# SolderingStation_Control.net
KiCad netlist of a schematic drawn in Altium Designer
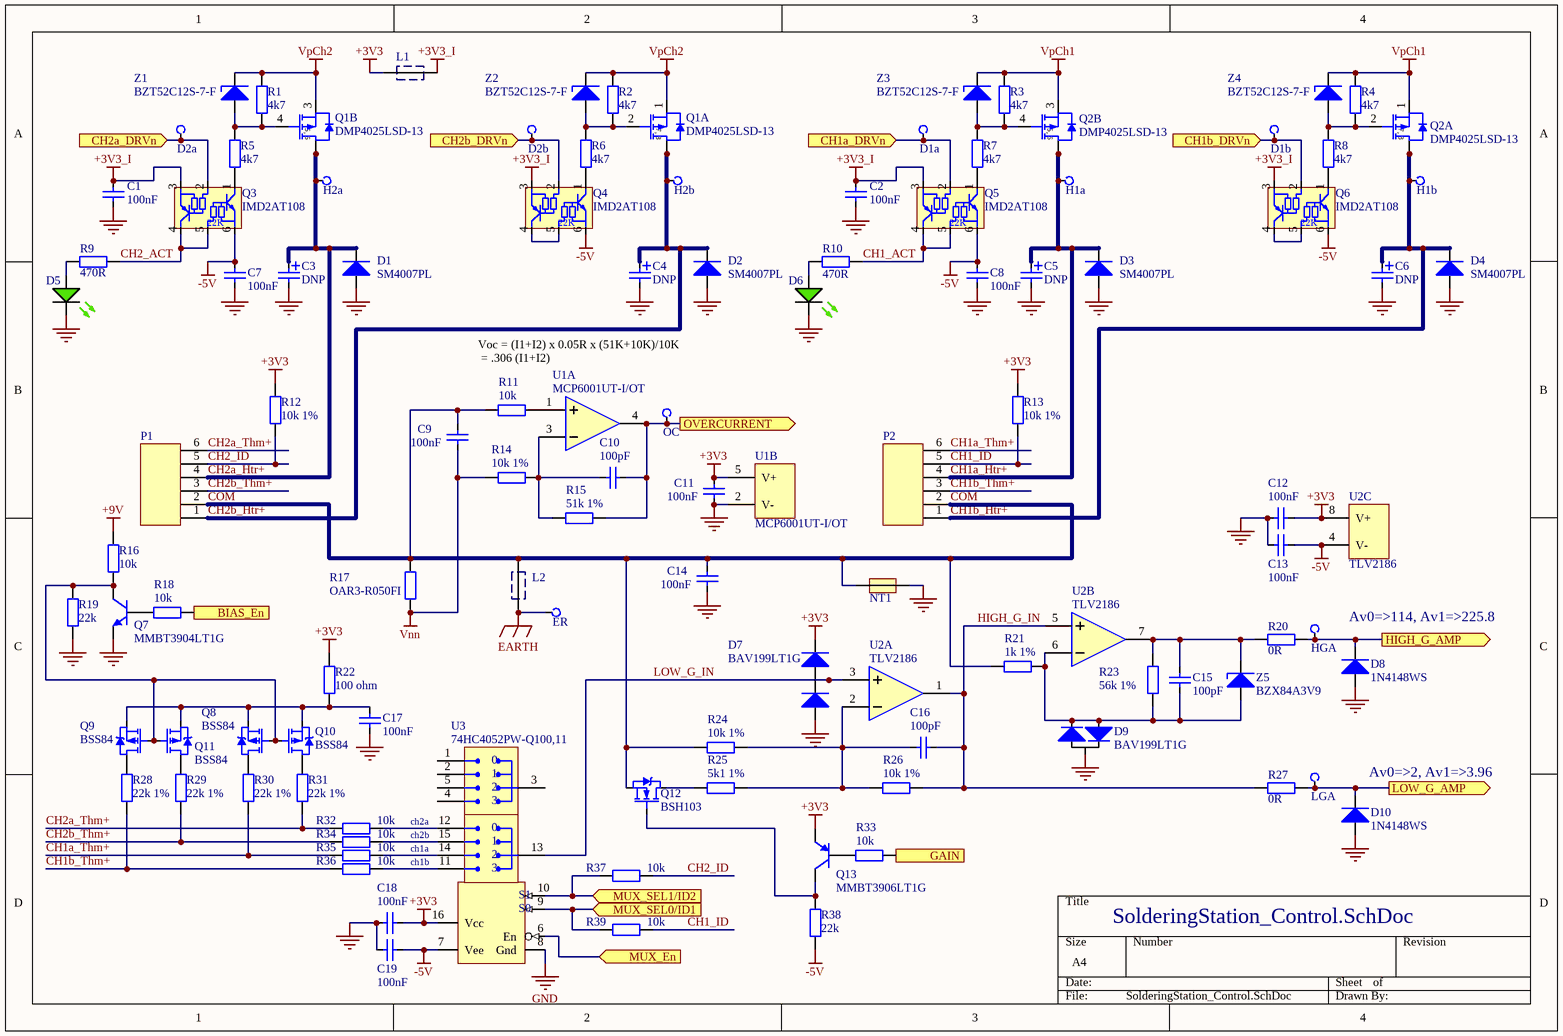
[diagram p0: SolderingStation_Control.SchDoc]

(export (version "E")
  (design (tool "Eeschema 10.0.6"))
  (components
    (comp (ref "C1")
      (value "100nF")
      (footprint "CCNP1608-0603")
      (description "Capacitor non-polar SMT 0603")
      (fields
        (field (name "MANUFACTURER") "Generic Components")
        (field (name "PUBLISHER") "Altium Hobart Technology Centre")
      )
      (libsource (lib "MyLibrary") (part "Cap_CCNP_0603"))
    )
    (comp (ref "C2")
      (value "100nF")
      (footprint "CCNP1608-0603")
      (description "Capacitor non-polar SMT 0603")
      (fields
        (field (name "MANUFACTURER") "Generic Components")
        (field (name "PUBLISHER") "Altium Hobart Technology Centre")
      )
      (libsource (lib "MyLibrary") (part "Cap_CCNP_0603"))
    )
    (comp (ref "C3")
      (value "DNP")
      (footprint "CC2012-0805")
      (description "Capacitor SMT 0805")
      (fields
        (field (name "MANUFACTURER") "Generic Components")
        (field (name "PUBLISHER") "Altium Hobart Technology Centre")
      )
      (libsource (lib "MyLibrary") (part "Cap_CC_0805"))
    )
    (comp (ref "C4")
      (value "DNP")
      (footprint "CC2012-0805")
      (description "Capacitor SMT 0805")
      (fields
        (field (name "MANUFACTURER") "Generic Components")
        (field (name "PUBLISHER") "Altium Hobart Technology Centre")
      )
      (libsource (lib "MyLibrary") (part "Cap_CC_0805"))
    )
    (comp (ref "C5")
      (value "DNP")
      (footprint "CC2012-0805")
      (description "Capacitor SMT 0805")
      (fields
        (field (name "MANUFACTURER") "Generic Components")
        (field (name "PUBLISHER") "Altium Hobart Technology Centre")
      )
      (libsource (lib "MyLibrary") (part "Cap_CC_0805"))
    )
    (comp (ref "C6")
      (value "DNP")
      (footprint "CC2012-0805")
      (description "Capacitor SMT 0805")
      (fields
        (field (name "MANUFACTURER") "Generic Components")
        (field (name "PUBLISHER") "Altium Hobart Technology Centre")
      )
      (libsource (lib "MyLibrary") (part "Cap_CC_0805"))
    )
    (comp (ref "C7")
      (value "100nF")
      (footprint "CCNP1608-0603")
      (description "Capacitor non-polar SMT 0603")
      (fields
        (field (name "MANUFACTURER") "Generic Components")
        (field (name "PUBLISHER") "Altium Hobart Technology Centre")
      )
      (libsource (lib "MyLibrary") (part "Cap_CCNP_0603"))
    )
    (comp (ref "C8")
      (value "100nF")
      (footprint "CCNP1608-0603")
      (description "Capacitor non-polar SMT 0603")
      (fields
        (field (name "MANUFACTURER") "Generic Components")
        (field (name "PUBLISHER") "Altium Hobart Technology Centre")
      )
      (libsource (lib "MyLibrary") (part "Cap_CCNP_0603"))
    )
    (comp (ref "C9")
      (value "100nF")
      (footprint "CCNP1608-0603")
      (description "Capacitor non-polar SMT 0603")
      (fields
        (field (name "MANUFACTURER") "Generic Components")
        (field (name "PUBLISHER") "Altium Hobart Technology Centre")
      )
      (libsource (lib "MyLibrary") (part "Cap_CCNP_0603"))
    )
    (comp (ref "C10")
      (value "100pF")
      (footprint "CCNP1608-0603")
      (description "Capacitor non-polar SMT 0603")
      (fields
        (field (name "MANUFACTURER") "Generic Components")
        (field (name "PUBLISHER") "Altium Hobart Technology Centre")
      )
      (libsource (lib "MyLibrary") (part "Cap_CCNP_0603"))
    )
    (comp (ref "C11")
      (value "100nF")
      (footprint "CCNP1608-0603")
      (description "Capacitor non-polar SMT 0603")
      (fields
        (field (name "MANUFACTURER") "Generic Components")
        (field (name "PUBLISHER") "Altium Hobart Technology Centre")
      )
      (libsource (lib "MyLibrary") (part "Cap_CCNP_0603"))
    )
    (comp (ref "C12")
      (value "100nF")
      (footprint "CCNP1608-0603")
      (description "Capacitor non-polar SMT 0603")
      (fields
        (field (name "MANUFACTURER") "Generic Components")
        (field (name "PUBLISHER") "Altium Hobart Technology Centre")
      )
      (libsource (lib "MyLibrary") (part "Cap_CCNP_0603"))
    )
    (comp (ref "C13")
      (value "100nF")
      (footprint "CCNP1608-0603")
      (description "Capacitor non-polar SMT 0603")
      (fields
        (field (name "MANUFACTURER") "Generic Components")
        (field (name "PUBLISHER") "Altium Hobart Technology Centre")
      )
      (libsource (lib "MyLibrary") (part "Cap_CCNP_0603"))
    )
    (comp (ref "C14")
      (value "100nF")
      (footprint "CCNP1608-0603")
      (description "Capacitor non-polar SMT 0603")
      (fields
        (field (name "MANUFACTURER") "Generic Components")
        (field (name "PUBLISHER") "Altium Hobart Technology Centre")
      )
      (libsource (lib "MyLibrary") (part "Cap_CCNP_0603"))
    )
    (comp (ref "C15")
      (value "100pF")
      (footprint "CCNP1608-0603")
      (description "Capacitor non-polar SMT 0603")
      (fields
        (field (name "MANUFACTURER") "Generic Components")
        (field (name "PUBLISHER") "Altium Hobart Technology Centre")
      )
      (libsource (lib "MyLibrary") (part "Cap_CCNP_0603"))
    )
    (comp (ref "C16")
      (value "100pF")
      (footprint "CCNP1608-0603")
      (description "Capacitor non-polar SMT 0603")
      (fields
        (field (name "MANUFACTURER") "Generic Components")
        (field (name "PUBLISHER") "Altium Hobart Technology Centre")
      )
      (libsource (lib "MyLibrary") (part "Cap_CCNP_0603"))
    )
    (comp (ref "C17")
      (value "100nF")
      (footprint "CCNP1608-0603")
      (description "Capacitor non-polar SMT 0603")
      (fields
        (field (name "MANUFACTURER") "Generic Components")
        (field (name "PUBLISHER") "Altium Hobart Technology Centre")
      )
      (libsource (lib "MyLibrary") (part "Cap_CCNP_0603"))
    )
    (comp (ref "C18")
      (value "100nF")
      (footprint "CCNP1608-0603")
      (description "Capacitor non-polar SMT 0603")
      (fields
        (field (name "MANUFACTURER") "Generic Components")
        (field (name "PUBLISHER") "Altium Hobart Technology Centre")
      )
      (libsource (lib "MyLibrary") (part "Cap_CCNP_0603"))
    )
    (comp (ref "C19")
      (value "100nF")
      (footprint "CCNP1608-0603")
      (description "Capacitor non-polar SMT 0603")
      (fields
        (field (name "MANUFACTURER") "Generic Components")
        (field (name "PUBLISHER") "Altium Hobart Technology Centre")
      )
      (libsource (lib "MyLibrary") (part "Cap_CCNP_0603"))
    )
    (comp (ref "D1")
      (value "SM4007PL")
      (footprint "SOD-123FL")
      (description "Diodes - General Purpose, 1kV 1A 1.1V 1A SOD-123FL")
      (libsource (lib "MyLibrary") (part "SM4007PL"))
    )
    (comp (ref "D1a")
      (value "Drive1")
      (footprint "PCBPIN - 0.7mm")
      (description "Test Point")
      (libsource (lib "MySchLib") (part "TP"))
    )
    (comp (ref "D1b")
      (value "Drive2")
      (footprint "PCBPIN - 0.7mm")
      (description "Test Point")
      (libsource (lib "MySchLib") (part "TP"))
    )
    (comp (ref "D2")
      (value "SM4007PL")
      (footprint "SOD-123FL")
      (description "Diodes - General Purpose, 1kV 1A 1.1V 1A SOD-123FL")
      (libsource (lib "MyLibrary") (part "SM4007PL"))
    )
    (comp (ref "D2a")
      (value "Drive2")
      (footprint "PCBPIN - 0.7mm")
      (description "Test Point")
      (libsource (lib "MySchLib") (part "TP"))
    )
    (comp (ref "D2b")
      (value "Drive2")
      (footprint "PCBPIN - 0.7mm")
      (description "Test Point")
      (libsource (lib "MySchLib") (part "TP"))
    )
    (comp (ref "D3")
      (value "SM4007PL")
      (footprint "SOD-123FL")
      (description "Diodes - General Purpose, 1kV 1A 1.1V 1A SOD-123FL")
      (libsource (lib "MyLibrary") (part "SM4007PL"))
    )
    (comp (ref "D4")
      (value "SM4007PL")
      (footprint "SOD-123FL")
      (description "Diodes - General Purpose, 1kV 1A 1.1V 1A SOD-123FL")
      (libsource (lib "MyLibrary") (part "SM4007PL"))
    )
    (comp (ref "D5")
      (value "LED")
      (footprint "LED3MM-GREEN - 10mm Proud")
      (description "3mm Green LED")
      (fields (field (name "MANUFACTURER") "Generic Components") (field (name "PUBLISHER") "Altium Limited"))
      (libsource (lib "MySchLib") (part "LED_3MM_GREEN"))
    )
    (comp (ref "D6")
      (value "LED")
      (footprint "LED3MM-GREEN - 10mm Proud")
      (description "3mm Green LED")
      (fields (field (name "MANUFACTURER") "Generic Components") (field (name "PUBLISHER") "Altium Limited"))
      (libsource (lib "MySchLib") (part "LED_3MM_GREEN"))
    )
    (comp (ref "D7")
      (value "BAV199LT1G")
      (footprint "SOT23_M")
      (description "Dual Series low-leakage switching diodes, 3-Pin SOT-23")
      (libsource (lib "MySchLib") (part "BAV199LT1G"))
    )
    (comp (ref "D8")
      (value "1N4148WS")
      (footprint "SOD-323")
      (description "Switching Diode 100V 150mA 1.25V@150mA 4ns SOD-323")
      (libsource (lib "MyLibrary") (part "1N4148WS"))
    )
    (comp (ref "D9")
      (value "BAV199LT1G")
      (footprint "SOT23_M")
      (description "Dual Series low-leakage switching diodes, 3-Pin SOT-23")
      (libsource (lib "MyLibrary") (part "BAV199LT1G"))
    )
    (comp (ref "D10")
      (value "1N4148WS")
      (footprint "SOD-323")
      (description "Switching Diode 100V 150mA 1.25V@150mA 4ns SOD-323")
      (libsource (lib "MyLibrary") (part "1N4148WS"))
    )
    (comp (ref "ER")
      (value "Gnd")
      (footprint "PCBPIN - 0.7mm")
      (description "Test Point")
      (libsource (lib "") (part "TP_1"))
    )
    (comp (ref "H1a")
      (value "Heater1")
      (footprint "PCBPIN - 0.7mm")
      (description "Test Point")
      (libsource (lib "") (part "TP_1"))
    )
    (comp (ref "H1b")
      (value "Heater2")
      (footprint "PCBPIN - 0.7mm")
      (description "Test Point")
      (libsource (lib "") (part "TP_1"))
    )
    (comp (ref "H2a")
      (value "Heater2")
      (footprint "PCBPIN - 0.7mm")
      (description "Test Point")
      (libsource (lib "") (part "TP_1"))
    )
    (comp (ref "H2b")
      (value "Heater2")
      (footprint "PCBPIN - 0.7mm")
      (description "Test Point")
      (libsource (lib "") (part "TP_1"))
    )
    (comp (ref "HGA")
      (value "TC1")
      (footprint "PCBPIN - 0.7mm")
      (description "Test Point")
      (libsource (lib "MySchLib") (part "TP"))
    )
    (comp (ref "L1")
      (value "Ferrite Bead")
      (footprint "FB2012-0805")
      (description "Ferrite Bead SMT 0805, TDK MPZ2012S102AT, 0.15OHM, 1.5A")
      (libsource (lib "MySchLib") (part "Ferrite Bead 0805"))
    )
    (comp (ref "L2")
      (value "Ferrite Bead")
      (footprint "FB2012-0805")
      (description "Ferrite Bead SMT 0805, TDK MPZ2012S102AT, 0.15OHM, 1.5A")
      (libsource (lib "MySchLib") (part "Ferrite Bead 0805"))
    )
    (comp (ref "LGA")
      (value "NTC1")
      (footprint "PCBPIN - 0.7mm")
      (description "Test Point")
      (libsource (lib "MySchLib") (part "TP"))
    )
    (comp (ref "NT1")
      (value "NetTieVia")
      (footprint "NetTieVia")
      (libsource (lib "MyLibrary") (part "NetTieVia"))
    )
    (comp (ref "OC")
      (value "Overcurrent")
      (footprint "PCBPIN - 0.7mm")
      (description "Test Point")
      (libsource (lib "MySchLib") (part "TP"))
    )
    (comp (ref "P1")
      (value "MOLEX-43045-0612")
      (footprint "MOLEX-43045-0612")
      (description "Wire-To-Board Connector, With Polarizing Peg, 3 mm, 6 Contacts, Header, Micro-Fit 3.0 43045 Series")
      (libsource (lib "MySchLib") (part "MOLEX-43045-0612"))
    )
    (comp (ref "P2")
      (value "MOLEX-43045-0612")
      (footprint "MOLEX-43045-0612")
      (description "Wire-To-Board Connector, With Polarizing Peg, 3 mm, 6 Contacts, Header, Micro-Fit 3.0 43045 Series")
      (libsource (lib "MySchLib") (part "MOLEX-43045-0612"))
    )
    (comp (ref "Q1")
      (value "DMP4025LSD-13")
      (footprint "SO-8_M")
      (description "P-Channel dual MOSFET, 40 V, 7.6 A, 0.018 ohm, SOIC, Surface Mount")
      (libsource (lib "MyLibrary") (part "DMP4025LSD-13"))
    )
    (comp (ref "Q2")
      (value "DMP4025LSD-13")
      (footprint "SO-8_M")
      (description "P-Channel dual MOSFET, 40 V, 7.6 A, 0.018 ohm, SOIC, Surface Mount")
      (libsource (lib "MyLibrary") (part "DMP4025LSD-13"))
    )
    (comp (ref "Q3")
      (value "IMD2AT108")
      (footprint "SOT457_N")
      (description "Pre-Biased NPN and PNP pair, 50 V, 100 mA, 22 kohm, 22 kohm")
      (libsource (lib "MyLibrary") (part "IMD2AT108"))
    )
    (comp (ref "Q4")
      (value "IMD2AT108")
      (footprint "SOT457_N")
      (description "Pre-Biased NPN and PNP pair, 50 V, 100 mA, 22 kohm, 22 kohm")
      (libsource (lib "MyLibrary") (part "IMD2AT108"))
    )
    (comp (ref "Q5")
      (value "IMD2AT108")
      (footprint "SOT457_N")
      (description "Pre-Biased NPN and PNP pair, 50 V, 100 mA, 22 kohm, 22 kohm")
      (libsource (lib "MyLibrary") (part "IMD2AT108"))
    )
    (comp (ref "Q6")
      (value "IMD2AT108")
      (footprint "SOT457_N")
      (description "Pre-Biased NPN and PNP pair, 50 V, 100 mA, 22 kohm, 22 kohm")
      (libsource (lib "MyLibrary") (part "IMD2AT108"))
    )
    (comp (ref "Q7")
      (value "MMBT3904LT1G")
      (footprint "SOT23_N")
      (description "General Purpose Transistor, NPN Silicon, 3-Pin SOT-23, Pb-Free, Tape and Reel")
      (fields (field (name "MANUFACTURER") "On Semiconductor"))
      (libsource (lib "MyLibrary") (part "MMBT3904LT1G"))
    )
    (comp (ref "Q8")
      (value "BSS84")
      (footprint "SOT23_M")
      (description "P-Channel Enhancement Mode FET -0.13 A, -50 V,  RDS(ON) = 10R at VGS = -5 V")
      (libsource (lib "MySchLib") (part "BSS84"))
    )
    (comp (ref "Q9")
      (value "BSS84")
      (footprint "SOT23_M")
      (description "P-Channel Enhancement Mode FET -0.13 A, -50 V,  RDS(ON) = 10R at VGS = -5 V")
      (libsource (lib "MySchLib") (part "BSS84"))
    )
    (comp (ref "Q10")
      (value "BSS84")
      (footprint "SOT23_M")
      (description "P-Channel Enhancement Mode FET -0.13 A, -50 V,  RDS(ON) = 10R at VGS = -5 V")
      (libsource (lib "MySchLib") (part "BSS84"))
    )
    (comp (ref "Q11")
      (value "BSS84")
      (footprint "SOT23_M")
      (description "P-Channel Enhancement Mode FET -0.13 A, -50 V,  RDS(ON) = 10R at VGS = -5 V")
      (libsource (lib "MySchLib") (part "BSS84"))
    )
    (comp (ref "Q12")
      (value "BSH103")
      (footprint "SOT23_N")
      (description "N-channel enhancement mode FET, , 30 V, 850 mA, 0.4 ohm, SOT23")
      (libsource (lib "MyLibrary") (part "BSH103"))
    )
    (comp (ref "Q13")
      (value "MMBT3906LT1G")
      (footprint "SOT23_N")
      (description "General Purpose Transistor, PNP Silicon, 3-Pin SOT-23, Pb-Free, Tape and Reel")
      (fields (field (name "MANUFACTURER") "On Semiconductor"))
      (libsource (lib "MyLibrary") (part "MMBT3906LT1G"))
    )
    (comp (ref "R1")
      (value "4k7")
      (footprint "CR1608-0603_N")
      (description "Resistor SMT 0603")
      (fields
        (field (name "MANUFACTURER") "Generic Components")
        (field (name "PUBLISHER") "Altium Hobart Technology Centre")
      )
      (libsource (lib "") (part "Res_CR0603_1"))
    )
    (comp (ref "R2")
      (value "4k7")
      (footprint "CR1608-0603_N")
      (description "Resistor SMT 0603")
      (fields
        (field (name "MANUFACTURER") "Generic Components")
        (field (name "PUBLISHER") "Altium Hobart Technology Centre")
      )
      (libsource (lib "") (part "Res_CR0603_1"))
    )
    (comp (ref "R3")
      (value "4k7")
      (footprint "CR1608-0603_N")
      (description "Resistor SMT 0603")
      (fields
        (field (name "MANUFACTURER") "Generic Components")
        (field (name "PUBLISHER") "Altium Hobart Technology Centre")
      )
      (libsource (lib "") (part "Res_CR0603_1"))
    )
    (comp (ref "R4")
      (value "4k7")
      (footprint "CR1608-0603_N")
      (description "Resistor SMT 0603")
      (fields
        (field (name "MANUFACTURER") "Generic Components")
        (field (name "PUBLISHER") "Altium Hobart Technology Centre")
      )
      (libsource (lib "") (part "Res_CR0603_1"))
    )
    (comp (ref "R5")
      (value "4k7")
      (footprint "CR1608-0603_N")
      (description "Resistor SMT 0603")
      (fields
        (field (name "MANUFACTURER") "Generic Components")
        (field (name "PUBLISHER") "Altium Hobart Technology Centre")
      )
      (libsource (lib "") (part "Res_CR0603_1"))
    )
    (comp (ref "R6")
      (value "4k7")
      (footprint "CR1608-0603_N")
      (description "Resistor SMT 0603")
      (fields
        (field (name "MANUFACTURER") "Generic Components")
        (field (name "PUBLISHER") "Altium Hobart Technology Centre")
      )
      (libsource (lib "") (part "Res_CR0603_1"))
    )
    (comp (ref "R7")
      (value "4k7")
      (footprint "CR1608-0603_N")
      (description "Resistor SMT 0603")
      (fields
        (field (name "MANUFACTURER") "Generic Components")
        (field (name "PUBLISHER") "Altium Hobart Technology Centre")
      )
      (libsource (lib "") (part "Res_CR0603_1"))
    )
    (comp (ref "R8")
      (value "4k7")
      (footprint "CR1608-0603_N")
      (description "Resistor SMT 0603")
      (fields
        (field (name "MANUFACTURER") "Generic Components")
        (field (name "PUBLISHER") "Altium Hobart Technology Centre")
      )
      (libsource (lib "") (part "Res_CR0603_1"))
    )
    (comp (ref "R9")
      (value "470R")
      (footprint "CR1608-0603_N")
      (description "Resistor SMT 0603")
      (fields
        (field (name "MANUFACTURER") "Generic Components")
        (field (name "PUBLISHER") "Altium Hobart Technology Centre")
      )
      (libsource (lib "MyLibrary") (part "Res_CR0603"))
    )
    (comp (ref "R10")
      (value "470R")
      (footprint "CR1608-0603_N")
      (description "Resistor SMT 0603")
      (fields
        (field (name "MANUFACTURER") "Generic Components")
        (field (name "PUBLISHER") "Altium Hobart Technology Centre")
      )
      (libsource (lib "MyLibrary") (part "Res_CR0603"))
    )
    (comp (ref "R11")
      (value "10k")
      (footprint "CR1608-0603_N")
      (description "Resistor SMT 0603")
      (fields
        (field (name "MANUFACTURER") "Generic Components")
        (field (name "PUBLISHER") "Altium Hobart Technology Centre")
      )
      (libsource (lib "") (part "Res_CR0603_3"))
    )
    (comp (ref "R12")
      (value "10k 1%")
      (footprint "CR1608-0603_N")
      (description "Resistor SMT 0603")
      (fields
        (field (name "MANUFACTURER") "Generic Components")
        (field (name "PUBLISHER") "Altium Hobart Technology Centre")
      )
      (libsource (lib "") (part "Res_CR0603_1"))
    )
    (comp (ref "R13")
      (value "10k 1%")
      (footprint "CR1608-0603_N")
      (description "Resistor SMT 0603")
      (fields
        (field (name "MANUFACTURER") "Generic Components")
        (field (name "PUBLISHER") "Altium Hobart Technology Centre")
      )
      (libsource (lib "") (part "Res_CR0603_1"))
    )
    (comp (ref "R14")
      (value "10k 1%")
      (footprint "CR1608-0603_N")
      (description "Resistor SMT 0603")
      (fields
        (field (name "MANUFACTURER") "Generic Components")
        (field (name "PUBLISHER") "Altium Hobart Technology Centre")
      )
      (libsource (lib "") (part "Res_CR0603_3"))
    )
    (comp (ref "R15")
      (value "51k 1%")
      (footprint "CR1608-0603_N")
      (description "Resistor SMT 0603")
      (fields
        (field (name "MANUFACTURER") "Generic Components")
        (field (name "PUBLISHER") "Altium Hobart Technology Centre")
      )
      (libsource (lib "MyLibrary") (part "Res_CR0603"))
    )
    (comp (ref "R16")
      (value "10k")
      (footprint "CR1608-0603_N")
      (description "Resistor SMT 0603")
      (fields
        (field (name "MANUFACTURER") "Generic Components")
        (field (name "PUBLISHER") "Altium Hobart Technology Centre")
      )
      (libsource (lib "") (part "Res_CR0603_2"))
    )
    (comp (ref "R17")
      (value "OAR3-R050FI")
      (footprint "OAR3-R050FI")
      (description "Current Sense Resistor, 0.05 ohm, OAR Series, 3 W, Metal Strip, Radial Leaded, 1%")
      (libsource (lib "MySchLib") (part "OAR3-R050FI"))
    )
    (comp (ref "R18")
      (value "10k")
      (footprint "CR1608-0603_N")
      (description "Resistor SMT 0603")
      (fields
        (field (name "MANUFACTURER") "Generic Components")
        (field (name "PUBLISHER") "Altium Hobart Technology Centre")
      )
      (libsource (lib "MyLibrary") (part "Res_CR0603"))
    )
    (comp (ref "R19")
      (value "22k")
      (footprint "CR1608-0603_N")
      (description "Resistor SMT 0603")
      (fields
        (field (name "MANUFACTURER") "Generic Components")
        (field (name "PUBLISHER") "Altium Hobart Technology Centre")
      )
      (libsource (lib "") (part "Res_CR0603_1"))
    )
    (comp (ref "R20")
      (value "0R")
      (footprint "CR1608-0603_N")
      (description "Resistor SMT 0603")
      (fields
        (field (name "MANUFACTURER") "Generic Components")
        (field (name "PUBLISHER") "Altium Hobart Technology Centre")
      )
      (libsource (lib "") (part "Res_CR0603_2"))
    )
    (comp (ref "R21")
      (value "1k 1%")
      (footprint "CR1608-0603_N")
      (description "Resistor SMT 0603")
      (fields
        (field (name "MANUFACTURER") "Generic Components")
        (field (name "PUBLISHER") "Altium Hobart Technology Centre")
      )
      (libsource (lib "") (part "Res_CR0603_3"))
    )
    (comp (ref "R22")
      (value "100 ohm")
      (footprint "CR1608-0603_N")
      (description "Resistor SMT 0603")
      (fields
        (field (name "MANUFACTURER") "Generic Components")
        (field (name "PUBLISHER") "Altium Hobart Technology Centre")
      )
      (libsource (lib "") (part "Res_CR0603_3"))
    )
    (comp (ref "R23")
      (value "56k 1%")
      (footprint "CR1608-0603_N")
      (description "Resistor SMT 0603")
      (fields
        (field (name "MANUFACTURER") "Generic Components")
        (field (name "PUBLISHER") "Altium Hobart Technology Centre")
      )
      (libsource (lib "") (part "Res_CR0603_1"))
    )
    (comp (ref "R24")
      (value "10k 1%")
      (footprint "CR1608-0603_N")
      (description "Resistor SMT 0603")
      (fields
        (field (name "MANUFACTURER") "Generic Components")
        (field (name "PUBLISHER") "Altium Hobart Technology Centre")
      )
      (libsource (lib "MyLibrary") (part "Res_CR0603"))
    )
    (comp (ref "R25")
      (value "5k1 1%")
      (footprint "CR1608-0603_N")
      (description "Resistor SMT 0603")
      (fields
        (field (name "MANUFACTURER") "Generic Components")
        (field (name "PUBLISHER") "Altium Hobart Technology Centre")
      )
      (libsource (lib "") (part "Res_CR0603_2"))
    )
    (comp (ref "R26")
      (value "10k 1%")
      (footprint "CR1608-0603_N")
      (description "Resistor SMT 0603")
      (fields
        (field (name "MANUFACTURER") "Generic Components")
        (field (name "PUBLISHER") "Altium Hobart Technology Centre")
      )
      (libsource (lib "MyLibrary") (part "Res_CR0603"))
    )
    (comp (ref "R27")
      (value "0R")
      (footprint "CR1608-0603_N")
      (description "Resistor SMT 0603")
      (fields
        (field (name "MANUFACTURER") "Generic Components")
        (field (name "PUBLISHER") "Altium Hobart Technology Centre")
      )
      (libsource (lib "") (part "Res_CR0603_2"))
    )
    (comp (ref "R28")
      (value "22k 1%")
      (footprint "CR1608-0603_N")
      (description "Resistor SMT 0603")
      (fields
        (field (name "MANUFACTURER") "Generic Components")
        (field (name "PUBLISHER") "Altium Hobart Technology Centre")
      )
      (libsource (lib "MyLibrary") (part "Res_CR0603"))
    )
    (comp (ref "R29")
      (value "22k 1%")
      (footprint "CR1608-0603_N")
      (description "Resistor SMT 0603")
      (fields
        (field (name "MANUFACTURER") "Generic Components")
        (field (name "PUBLISHER") "Altium Hobart Technology Centre")
      )
      (libsource (lib "MyLibrary") (part "Res_CR0603"))
    )
    (comp (ref "R30")
      (value "22k 1%")
      (footprint "CR1608-0603_N")
      (description "Resistor SMT 0603")
      (fields
        (field (name "MANUFACTURER") "Generic Components")
        (field (name "PUBLISHER") "Altium Hobart Technology Centre")
      )
      (libsource (lib "") (part "Res_CR0603_1"))
    )
    (comp (ref "R31")
      (value "22k 1%")
      (footprint "CR1608-0603_N")
      (description "Resistor SMT 0603")
      (fields
        (field (name "MANUFACTURER") "Generic Components")
        (field (name "PUBLISHER") "Altium Hobart Technology Centre")
      )
      (libsource (lib "") (part "Res_CR0603_1"))
    )
    (comp (ref "R32")
      (value "10k")
      (footprint "CR1608-0603_N")
      (description "Resistor SMT 0603")
      (fields
        (field (name "MANUFACTURER") "Generic Components")
        (field (name "PUBLISHER") "Altium Hobart Technology Centre")
      )
      (libsource (lib "") (part "Res_CR0603_2"))
    )
    (comp (ref "R33")
      (value "10k")
      (footprint "CR1608-0603_N")
      (description "Resistor SMT 0603")
      (fields
        (field (name "MANUFACTURER") "Generic Components")
        (field (name "PUBLISHER") "Altium Hobart Technology Centre")
      )
      (libsource (lib "MyLibrary") (part "Res_CR0603"))
    )
    (comp (ref "R34")
      (value "10k")
      (footprint "CR1608-0603_N")
      (description "Resistor SMT 0603")
      (fields
        (field (name "MANUFACTURER") "Generic Components")
        (field (name "PUBLISHER") "Altium Hobart Technology Centre")
      )
      (libsource (lib "") (part "Res_CR0603_2"))
    )
    (comp (ref "R35")
      (value "10k")
      (footprint "CR1608-0603_N")
      (description "Resistor SMT 0603")
      (fields
        (field (name "MANUFACTURER") "Generic Components")
        (field (name "PUBLISHER") "Altium Hobart Technology Centre")
      )
      (libsource (lib "") (part "Res_CR0603_2"))
    )
    (comp (ref "R36")
      (value "10k")
      (footprint "CR1608-0603_N")
      (description "Resistor SMT 0603")
      (fields
        (field (name "MANUFACTURER") "Generic Components")
        (field (name "PUBLISHER") "Altium Hobart Technology Centre")
      )
      (libsource (lib "") (part "Res_CR0603_2"))
    )
    (comp (ref "R37")
      (value "10k")
      (footprint "CR1608-0603_N")
      (description "Resistor SMT 0603")
      (fields
        (field (name "MANUFACTURER") "Generic Components")
        (field (name "PUBLISHER") "Altium Hobart Technology Centre")
      )
      (libsource (lib "") (part "Res_CR0603_2"))
    )
    (comp (ref "R38")
      (value "22k")
      (footprint "CR1608-0603_N")
      (description "Resistor SMT 0603")
      (fields
        (field (name "MANUFACTURER") "Generic Components")
        (field (name "PUBLISHER") "Altium Hobart Technology Centre")
      )
      (libsource (lib "") (part "Res_CR0603_1"))
    )
    (comp (ref "R39")
      (value "10k")
      (footprint "CR1608-0603_N")
      (description "Resistor SMT 0603")
      (fields
        (field (name "MANUFACTURER") "Generic Components")
        (field (name "PUBLISHER") "Altium Hobart Technology Centre")
      )
      (libsource (lib "") (part "Res_CR0603_2"))
    )
    (comp (ref "U1")
      (value "MCP6001UT-I/OT")
      (footprint "SOT23-5_M")
      (description "Op-Amp, Single supply R-R in/out")
      (libsource (lib "MySchLib") (part "MCP6001UT-I/OT"))
    )
    (comp (ref "U2")
      (value "TLV2186")
      (footprint "SOIC127P600-8M")
      (description "Dual Precision,Rail-to-Rail Input and Output, 4.5-24V, Zero-Drift OperationalAmplifier")
      (libsource (lib "MySchLib") (part "TLV2186"))
    )
    (comp (ref "U3")
      (value "74HC4052PW-Q100,11")
      (footprint "TSSOP16_M")
      (description "Analog Multiplexer / Demultiplexer, 4:1, 2 Circuits, 225 ohm, 2V to 10V, TSSOP-16")
      (libsource (lib "MySchLib") (part "74HC4052PW-Q100,11"))
    )
    (comp (ref "Z1")
      (value "BZT52C12S-7-F")
      (footprint "SOD-323")
      (description "Surface Mount Zener Diode, 12-13 V, -65 to 150 degC, SOD-123")
      (libsource (lib "MySchLib") (part "BZT52C12S-7-F"))
    )
    (comp (ref "Z2")
      (value "BZT52C12S-7-F")
      (footprint "SOD-323")
      (description "Surface Mount Zener Diode, 12-13 V, -65 to 150 degC, SOD-123")
      (libsource (lib "MySchLib") (part "BZT52C12S-7-F"))
    )
    (comp (ref "Z3")
      (value "BZT52C12S-7-F")
      (footprint "SOD-323")
      (description "Surface Mount Zener Diode, 12-13 V, -65 to 150 degC, SOD-123")
      (libsource (lib "MySchLib") (part "BZT52C12S-7-F"))
    )
    (comp (ref "Z4")
      (value "BZT52C12S-7-F")
      (footprint "SOD-323")
      (description "Surface Mount Zener Diode, 12-13 V, -65 to 150 degC, SOD-123")
      (libsource (lib "MySchLib") (part "BZT52C12S-7-F"))
    )
    (comp (ref "Z5")
      (value "BZX84A3V9")
      (footprint "SOT23_M")
      (description "Zener Diode, 3.9V, 250mW, SOT-23, 1%, 150C")
      (fields
        (field (name "MANUFACTURER") "Generic Components")
        (field (name "PUBLISHER") "Altium Hobart Technology Centre")
      )
      (libsource (lib "MyLibrary") (part "BZX84A3V9"))
    )
  )
  (nets
    (net (code "1") (name "+3V3") (class "Default")
      (node (ref "C11") (pin "1") (pinfunction "1_1") (pintype "passive"))
      (node (ref "C12") (pin "1") (pinfunction "1_1") (pintype "passive"))
      (node (ref "C18") (pin "1") (pinfunction "1_1") (pintype "passive"))
      (node (ref "D7") (pin "2") (pinfunction "A2_2") (pintype "passive"))
      (node (ref "L1") (pin "1") (pinfunction "1_1") (pintype "passive"))
      (node (ref "Q13") (pin "2") (pinfunction "E_2") (pintype "passive"))
      (node (ref "R12") (pin "2") (pinfunction "2_2") (pintype "passive"))
      (node (ref "R13") (pin "2") (pinfunction "2_2") (pintype "passive"))
      (node (ref "R22") (pin "1") (pinfunction "1_1") (pintype "passive"))
      (node (ref "U1") (pin "5") (pinfunction "V+_5") (pintype "power_in"))
      (node (ref "U2") (pin "8") (pinfunction "V+_8") (pintype "power_in"))
      (node (ref "U3") (pin "16") (pinfunction "Vcc_16") (pintype "power_in"))
    )
    (net (code "2") (name "+3V3_I") (class "Default")
      (node (ref "C1") (pin "1") (pinfunction "1_1") (pintype "passive"))
      (node (ref "C2") (pin "1") (pinfunction "1_1") (pintype "passive"))
      (node (ref "L1") (pin "2") (pinfunction "2_2") (pintype "passive"))
      (node (ref "Q3") (pin "3") (pinfunction "E2_3") (pintype "passive"))
      (node (ref "Q4") (pin "3") (pinfunction "E2_3") (pintype "passive"))
      (node (ref "Q5") (pin "3") (pinfunction "E2_3") (pintype "passive"))
      (node (ref "Q6") (pin "3") (pinfunction "E2_3") (pintype "passive"))
    )
    (net (code "3") (name "+9V") (class "Default")
      (node (ref "R16") (pin "1") (pinfunction "1_1") (pintype "passive"))
    )
    (net (code "4") (name "-5V") (class "Default")
      (node (ref "C13") (pin "1") (pinfunction "1_1") (pintype "passive"))
      (node (ref "C19") (pin "1") (pinfunction "1_1") (pintype "passive"))
      (node (ref "C7") (pin "1") (pinfunction "1_1") (pintype "passive"))
      (node (ref "C8") (pin "1") (pinfunction "1_1") (pintype "passive"))
      (node (ref "Q3") (pin "6") (pinfunction "E1_6") (pintype "passive"))
      (node (ref "Q4") (pin "6") (pinfunction "E1_6") (pintype "passive"))
      (node (ref "Q5") (pin "6") (pinfunction "E1_6") (pintype "passive"))
      (node (ref "Q6") (pin "6") (pinfunction "E1_6") (pintype "passive"))
      (node (ref "R38") (pin "1") (pinfunction "1_1") (pintype "passive"))
      (node (ref "U2") (pin "4") (pinfunction "V-_4") (pintype "power_in"))
      (node (ref "U3") (pin "7") (pinfunction "Vee_7") (pintype "power_in"))
    )
    (net (code "5") (name "/BIAS_En") (class "Default")
      (node (ref "R18") (pin "2") (pinfunction "2_2") (pintype "passive"))
    )
    (net (code "6") (name "/CH1_ACT") (class "Default")
      (node (ref "Q5") (pin "4") (pinfunction "C2_4") (pintype "passive"))
      (node (ref "Q5") (pin "5") (pinfunction "B1_5") (pintype "passive"))
      (node (ref "R10") (pin "2") (pinfunction "2_2") (pintype "passive"))
    )
    (net (code "7") (name "/CH1_ID") (class "Default")
      (node (ref "P2") (pin "5") (pinfunction "5_5") (pintype "passive"))
      (node (ref "R13") (pin "1") (pinfunction "1_1") (pintype "passive"))
      (node (ref "R39") (pin "1") (pinfunction "1_1") (pintype "passive"))
    )
    (net (code "8") (name "/CH1a_DRVn") (class "Default")
      (node (ref "D1a") (pin "1") (pinfunction "TP_1") (pintype "passive"))
      (node (ref "Q5") (pin "2") (pinfunction "B2_2") (pintype "passive"))
    )
    (net (code "9") (name "/CH1a_Htr+") (class "Default")
      (node (ref "C5") (pin "1") (pinfunction "1_1") (pintype "passive"))
      (node (ref "D3") (pin "K") (pinfunction "K_K") (pintype "passive"))
      (node (ref "H1a") (pin "1") (pinfunction "TP_1") (pintype "passive"))
      (node (ref "P2") (pin "4") (pinfunction "4_4") (pintype "passive"))
      (node (ref "Q2") (pin "5") (pinfunction "D2_5") (pintype "passive"))
      (node (ref "Q2") (pin "6") (pinfunction "D2_6") (pintype "passive"))
    )
    (net (code "10") (name "/CH1a_Thm+") (class "Default")
      (node (ref "P2") (pin "6") (pinfunction "6_6") (pintype "passive"))
      (node (ref "R30") (pin "1") (pinfunction "1_1") (pintype "passive"))
      (node (ref "R35") (pin "2") (pinfunction "2_2") (pintype "passive"))
    )
    (net (code "11") (name "/CH1b_DRVn") (class "Default")
      (node (ref "D1b") (pin "1") (pinfunction "TP_1") (pintype "passive"))
      (node (ref "Q6") (pin "2") (pinfunction "B2_2") (pintype "passive"))
    )
    (net (code "12") (name "/CH1b_Htr+") (class "Default")
      (node (ref "C6") (pin "1") (pinfunction "1_1") (pintype "passive"))
      (node (ref "D4") (pin "K") (pinfunction "K_K") (pintype "passive"))
      (node (ref "H1b") (pin "1") (pinfunction "TP_1") (pintype "passive"))
      (node (ref "P2") (pin "1") (pinfunction "1_1") (pintype "passive"))
      (node (ref "Q2") (pin "7") (pinfunction "D1_7") (pintype "passive"))
      (node (ref "Q2") (pin "8") (pinfunction "D1_8") (pintype "passive"))
    )
    (net (code "13") (name "/CH1b_Thm+") (class "Default")
      (node (ref "P2") (pin "3") (pinfunction "3_3") (pintype "passive"))
      (node (ref "R28") (pin "1") (pinfunction "1_1") (pintype "passive"))
      (node (ref "R36") (pin "2") (pinfunction "2_2") (pintype "passive"))
    )
    (net (code "14") (name "/CH2_ACT") (class "Default")
      (node (ref "Q3") (pin "4") (pinfunction "C2_4") (pintype "passive"))
      (node (ref "Q3") (pin "5") (pinfunction "B1_5") (pintype "passive"))
      (node (ref "R9") (pin "2") (pinfunction "2_2") (pintype "passive"))
    )
    (net (code "15") (name "/CH2_ID") (class "Default")
      (node (ref "P1") (pin "5") (pinfunction "5_5") (pintype "passive"))
      (node (ref "R12") (pin "1") (pinfunction "1_1") (pintype "passive"))
      (node (ref "R37") (pin "1") (pinfunction "1_1") (pintype "passive"))
    )
    (net (code "16") (name "/CH2a_DRVn") (class "Default")
      (node (ref "D2a") (pin "1") (pinfunction "TP_1") (pintype "passive"))
      (node (ref "Q3") (pin "2") (pinfunction "B2_2") (pintype "passive"))
    )
    (net (code "17") (name "/CH2a_Htr+") (class "Default")
      (node (ref "C3") (pin "1") (pinfunction "1_1") (pintype "passive"))
      (node (ref "D1") (pin "K") (pinfunction "K_K") (pintype "passive"))
      (node (ref "H2a") (pin "1") (pinfunction "TP_1") (pintype "passive"))
      (node (ref "P1") (pin "4") (pinfunction "4_4") (pintype "passive"))
      (node (ref "Q1") (pin "5") (pinfunction "D2_5") (pintype "passive"))
      (node (ref "Q1") (pin "6") (pinfunction "D2_6") (pintype "passive"))
    )
    (net (code "18") (name "/CH2a_Thm+") (class "Default")
      (node (ref "P1") (pin "6") (pinfunction "6_6") (pintype "passive"))
      (node (ref "R31") (pin "1") (pinfunction "1_1") (pintype "passive"))
      (node (ref "R32") (pin "2") (pinfunction "2_2") (pintype "passive"))
    )
    (net (code "19") (name "/CH2b_DRVn") (class "Default")
      (node (ref "D2b") (pin "1") (pinfunction "TP_1") (pintype "passive"))
      (node (ref "Q4") (pin "2") (pinfunction "B2_2") (pintype "passive"))
    )
    (net (code "20") (name "/CH2b_Htr+") (class "Default")
      (node (ref "C4") (pin "1") (pinfunction "1_1") (pintype "passive"))
      (node (ref "D2") (pin "K") (pinfunction "K_K") (pintype "passive"))
      (node (ref "H2b") (pin "1") (pinfunction "TP_1") (pintype "passive"))
      (node (ref "P1") (pin "1") (pinfunction "1_1") (pintype "passive"))
      (node (ref "Q1") (pin "7") (pinfunction "D1_7") (pintype "passive"))
      (node (ref "Q1") (pin "8") (pinfunction "D1_8") (pintype "passive"))
    )
    (net (code "21") (name "/CH2b_Thm+") (class "Default")
      (node (ref "P1") (pin "3") (pinfunction "3_3") (pintype "passive"))
      (node (ref "R29") (pin "1") (pinfunction "1_1") (pintype "passive"))
      (node (ref "R34") (pin "2") (pinfunction "2_2") (pintype "passive"))
    )
    (net (code "22") (name "/COM") (class "Default")
      (node (ref "C14") (pin "1") (pinfunction "1_1") (pintype "passive"))
      (node (ref "C9") (pin "1") (pinfunction "1_1") (pintype "passive"))
      (node (ref "L2") (pin "2") (pinfunction "2_2") (pintype "passive"))
      (node (ref "NT1") (pin "2") (pinfunction "2_2") (pintype "passive"))
      (node (ref "P1") (pin "2") (pinfunction "2_2") (pintype "passive"))
      (node (ref "P2") (pin "2") (pinfunction "2_2") (pintype "passive"))
      (node (ref "Q12") (pin "2") (pinfunction "S_2") (pintype "passive"))
      (node (ref "R11") (pin "2") (pinfunction "2_2") (pintype "passive"))
      (node (ref "R17") (pin "2") (pinfunction "2_2") (pintype "passive"))
      (node (ref "R21") (pin "2") (pinfunction "2_2") (pintype "passive"))
      (node (ref "R24") (pin "1") (pinfunction "1_1") (pintype "passive"))
    )
    (net (code "23") (name "/GAIN") (class "Default")
      (node (ref "R33") (pin "2") (pinfunction "2_2") (pintype "passive"))
    )
    (net (code "24") (name "/HIGH_G_AMP") (class "Default")
      (node (ref "D8") (pin "K") (pinfunction "K_K") (pintype "passive"))
      (node (ref "HGA") (pin "1") (pinfunction "TP_1") (pintype "passive"))
      (node (ref "R20") (pin "1") (pinfunction "1_1") (pintype "passive"))
    )
    (net (code "25") (name "/HIGH_G_IN") (class "Default")
      (node (ref "C16") (pin "2") (pinfunction "2_2") (pintype "passive"))
      (node (ref "R26") (pin "2") (pinfunction "2_2") (pintype "passive"))
      (node (ref "R27") (pin "2") (pinfunction "2_2") (pintype "passive"))
      (node (ref "U2") (pin "1") (pinfunction "A_1") (pintype "passive"))
      (node (ref "U2") (pin "5") (pinfunction "B+_5") (pintype "passive"))
    )
    (net (code "26") (name "/LOW_G_AMP") (class "Default")
      (node (ref "D10") (pin "K") (pinfunction "K_K") (pintype "passive"))
      (node (ref "LGA") (pin "1") (pinfunction "TP_1") (pintype "passive"))
      (node (ref "R27") (pin "1") (pinfunction "1_1") (pintype "passive"))
    )
    (net (code "27") (name "/LOW_G_IN") (class "Default")
      (node (ref "D7") (pin "3") (pinfunction "K_3") (pintype "passive"))
      (node (ref "U2") (pin "3") (pinfunction "A+_3") (pintype "passive"))
      (node (ref "U3") (pin "13") (pinfunction "1Z_13") (pintype "passive"))
    )
    (net (code "28") (name "/MUX_En") (class "Default")
      (node (ref "U3") (pin "6") (pinfunction "En_6") (pintype "input"))
    )
    (net (code "29") (name "/MUX_SEL0{slash}ID1") (class "Default")
      (node (ref "R39") (pin "2") (pinfunction "2_2") (pintype "passive"))
      (node (ref "U3") (pin "9") (pinfunction "S1_9") (pintype "input"))
    )
    (net (code "30") (name "/MUX_SEL1{slash}ID2") (class "Default")
      (node (ref "R37") (pin "2") (pinfunction "2_2") (pintype "passive"))
      (node (ref "U3") (pin "10") (pinfunction "S0_10") (pintype "input"))
    )
    (net (code "31") (name "/OVERCURRENT") (class "Default")
      (node (ref "C10") (pin "2") (pinfunction "2_2") (pintype "passive"))
      (node (ref "OC") (pin "1") (pinfunction "TP_1") (pintype "passive"))
      (node (ref "R15") (pin "2") (pinfunction "2_2") (pintype "passive"))
      (node (ref "U1") (pin "4") (pinfunction "Out_4") (pintype "passive"))
    )
    (net (code "32") (name "EARTH") (class "Default")
      (node (ref "ER") (pin "1") (pinfunction "TP_1") (pintype "passive"))
      (node (ref "L2") (pin "1") (pinfunction "1_1") (pintype "passive"))
    )
    (net (code "33") (name "GND") (class "Default")
      (node (ref "C1") (pin "2") (pinfunction "2_2") (pintype "passive"))
      (node (ref "C11") (pin "2") (pinfunction "2_2") (pintype "passive"))
      (node (ref "C12") (pin "2") (pinfunction "2_2") (pintype "passive"))
      (node (ref "C13") (pin "2") (pinfunction "2_2") (pintype "passive"))
      (node (ref "C14") (pin "2") (pinfunction "2_2") (pintype "passive"))
      (node (ref "C17") (pin "1") (pinfunction "1_1") (pintype "passive"))
      (node (ref "C18") (pin "2") (pinfunction "2_2") (pintype "passive"))
      (node (ref "C19") (pin "2") (pinfunction "2_2") (pintype "passive"))
      (node (ref "C2") (pin "2") (pinfunction "2_2") (pintype "passive"))
      (node (ref "C3") (pin "2") (pinfunction "2_2") (pintype "passive"))
      (node (ref "C4") (pin "2") (pinfunction "2_2") (pintype "passive"))
      (node (ref "C5") (pin "2") (pinfunction "2_2") (pintype "passive"))
      (node (ref "C6") (pin "2") (pinfunction "2_2") (pintype "passive"))
      (node (ref "C7") (pin "2") (pinfunction "2_2") (pintype "passive"))
      (node (ref "C8") (pin "2") (pinfunction "2_2") (pintype "passive"))
      (node (ref "D1") (pin "A") (pinfunction "A_A") (pintype "passive"))
      (node (ref "D10") (pin "A") (pinfunction "A_A") (pintype "passive"))
      (node (ref "D2") (pin "A") (pinfunction "A_A") (pintype "passive"))
      (node (ref "D3") (pin "A") (pinfunction "A_A") (pintype "passive"))
      (node (ref "D4") (pin "A") (pinfunction "A_A") (pintype "passive"))
      (node (ref "D5") (pin "K") (pinfunction "K_K") (pintype "passive"))
      (node (ref "D6") (pin "K") (pinfunction "K_K") (pintype "passive"))
      (node (ref "D7") (pin "1") (pinfunction "A1_1") (pintype "passive"))
      (node (ref "D8") (pin "A") (pinfunction "A_A") (pintype "passive"))
      (node (ref "D9") (pin "3") (pinfunction "K_3") (pintype "passive"))
      (node (ref "NT1") (pin "1") (pinfunction "1_1") (pintype "passive"))
      (node (ref "Q7") (pin "2") (pinfunction "E_2") (pintype "passive"))
      (node (ref "R19") (pin "1") (pinfunction "1_1") (pintype "passive"))
      (node (ref "U1") (pin "2") (pinfunction "V-_2") (pintype "power_in"))
      (node (ref "U3") (pin "8") (pinfunction "Gnd_8") (pintype "power_in"))
    )
    (net (code "34") (name "Net-(C15-Pad2)") (class "Default")
      (node (ref "C15") (pin "2") (pinfunction "2_2") (pintype "passive"))
      (node (ref "R20") (pin "2") (pinfunction "2_2") (pintype "passive"))
      (node (ref "R23") (pin "2") (pinfunction "2_2") (pintype "passive"))
      (node (ref "U2") (pin "7") (pinfunction "7_7") (pintype "passive"))
      (node (ref "Z5") (pin "K") (pinfunction "K_K") (pintype "passive"))
    )
    (net (code "35") (name "Net-(D5-PadA)") (class "Default")
      (node (ref "D5") (pin "A") (pinfunction "A_A") (pintype "passive"))
      (node (ref "R9") (pin "1") (pinfunction "1_1") (pintype "passive"))
    )
    (net (code "36") (name "Net-(D6-PadA)") (class "Default")
      (node (ref "D6") (pin "A") (pinfunction "A_A") (pintype "passive"))
      (node (ref "R10") (pin "1") (pinfunction "1_1") (pintype "passive"))
    )
    (net (code "37") (name "Net-(D9-A1)") (class "Default")
      (node (ref "C15") (pin "1") (pinfunction "1_1") (pintype "passive"))
      (node (ref "D9") (pin "1") (pinfunction "A1_1") (pintype "passive"))
      (node (ref "D9") (pin "2") (pinfunction "A2_2") (pintype "passive"))
      (node (ref "R21") (pin "1") (pinfunction "1_1") (pintype "passive"))
      (node (ref "R23") (pin "1") (pinfunction "1_1") (pintype "passive"))
      (node (ref "U2") (pin "6") (pinfunction "B-_6") (pintype "passive"))
      (node (ref "Z5") (pin "A") (pinfunction "A_A") (pintype "passive"))
    )
    (net (code "38") (name "Net-(Q1A-G1)") (class "Default")
      (node (ref "Q1") (pin "2") (pinfunction "G1_2") (pintype "passive"))
      (node (ref "R2") (pin "1") (pinfunction "1_1") (pintype "passive"))
      (node (ref "R6") (pin "2") (pinfunction "2_2") (pintype "passive"))
      (node (ref "Z2") (pin "A") (pinfunction "A_A") (pintype "passive"))
    )
    (net (code "39") (name "Net-(Q1B-G2)") (class "Default")
      (node (ref "Q1") (pin "4") (pinfunction "G2_4") (pintype "passive"))
      (node (ref "R1") (pin "1") (pinfunction "1_1") (pintype "passive"))
      (node (ref "R5") (pin "2") (pinfunction "2_2") (pintype "passive"))
      (node (ref "Z1") (pin "A") (pinfunction "A_A") (pintype "passive"))
    )
    (net (code "40") (name "Net-(Q2A-G1)") (class "Default")
      (node (ref "Q2") (pin "2") (pinfunction "G1_2") (pintype "passive"))
      (node (ref "R4") (pin "1") (pinfunction "1_1") (pintype "passive"))
      (node (ref "R8") (pin "2") (pinfunction "2_2") (pintype "passive"))
      (node (ref "Z4") (pin "A") (pinfunction "A_A") (pintype "passive"))
    )
    (net (code "41") (name "Net-(Q2B-G2)") (class "Default")
      (node (ref "Q2") (pin "4") (pinfunction "G2_4") (pintype "passive"))
      (node (ref "R3") (pin "1") (pinfunction "1_1") (pintype "passive"))
      (node (ref "R7") (pin "2") (pinfunction "2_2") (pintype "passive"))
      (node (ref "Z3") (pin "A") (pinfunction "A_A") (pintype "passive"))
    )
    (net (code "42") (name "Net-(Q3-C1)") (class "Default")
      (node (ref "Q3") (pin "1") (pinfunction "C1_1") (pintype "passive"))
      (node (ref "R5") (pin "1") (pinfunction "1_1") (pintype "passive"))
    )
    (net (code "43") (name "Net-(Q4-B1)") (class "Default")
      (node (ref "Q4") (pin "4") (pinfunction "C2_4") (pintype "passive"))
      (node (ref "Q4") (pin "5") (pinfunction "B1_5") (pintype "passive"))
    )
    (net (code "44") (name "Net-(Q4-C1)") (class "Default")
      (node (ref "Q4") (pin "1") (pinfunction "C1_1") (pintype "passive"))
      (node (ref "R6") (pin "1") (pinfunction "1_1") (pintype "passive"))
    )
    (net (code "45") (name "Net-(Q5-C1)") (class "Default")
      (node (ref "Q5") (pin "1") (pinfunction "C1_1") (pintype "passive"))
      (node (ref "R7") (pin "1") (pinfunction "1_1") (pintype "passive"))
    )
    (net (code "46") (name "Net-(Q6-B1)") (class "Default")
      (node (ref "Q6") (pin "4") (pinfunction "C2_4") (pintype "passive"))
      (node (ref "Q6") (pin "5") (pinfunction "B1_5") (pintype "passive"))
    )
    (net (code "47") (name "Net-(Q6-C1)") (class "Default")
      (node (ref "Q6") (pin "1") (pinfunction "C1_1") (pintype "passive"))
      (node (ref "R8") (pin "1") (pinfunction "1_1") (pintype "passive"))
    )
    (net (code "48") (name "Net-(Q7-B)") (class "Default")
      (node (ref "Q7") (pin "1") (pinfunction "B_1") (pintype "passive"))
      (node (ref "R18") (pin "1") (pinfunction "1_1") (pintype "passive"))
    )
    (net (code "49") (name "Net-(Q8-D)") (class "Default")
      (node (ref "Q8") (pin "3") (pinfunction "D_3") (pintype "passive"))
      (node (ref "R30") (pin "2") (pinfunction "2_2") (pintype "passive"))
    )
    (net (code "50") (name "Net-(Q9-D)") (class "Default")
      (node (ref "Q9") (pin "3") (pinfunction "D_3") (pintype "passive"))
      (node (ref "R28") (pin "2") (pinfunction "2_2") (pintype "passive"))
    )
    (net (code "51") (name "Net-(Q10-D)") (class "Default")
      (node (ref "Q10") (pin "3") (pinfunction "D_3") (pintype "passive"))
      (node (ref "R31") (pin "2") (pinfunction "2_2") (pintype "passive"))
    )
    (net (code "52") (name "Net-(Q10-G)") (class "Default")
      (node (ref "Q10") (pin "1") (pinfunction "G_1") (pintype "passive"))
      (node (ref "Q11") (pin "1") (pinfunction "G_1") (pintype "passive"))
      (node (ref "Q7") (pin "3") (pinfunction "C_3") (pintype "passive"))
      (node (ref "Q8") (pin "1") (pinfunction "G_1") (pintype "passive"))
      (node (ref "Q9") (pin "1") (pinfunction "G_1") (pintype "passive"))
      (node (ref "R16") (pin "2") (pinfunction "2_2") (pintype "passive"))
      (node (ref "R19") (pin "2") (pinfunction "2_2") (pintype "passive"))
    )
    (net (code "53") (name "Net-(Q10-S)") (class "Default")
      (node (ref "C17") (pin "2") (pinfunction "2_2") (pintype "passive"))
      (node (ref "Q10") (pin "2") (pinfunction "S_2") (pintype "passive"))
      (node (ref "Q11") (pin "2") (pinfunction "S_2") (pintype "passive"))
      (node (ref "Q8") (pin "2") (pinfunction "S_2") (pintype "passive"))
      (node (ref "Q9") (pin "2") (pinfunction "S_2") (pintype "passive"))
      (node (ref "R22") (pin "2") (pinfunction "2_2") (pintype "passive"))
    )
    (net (code "54") (name "Net-(Q11-D)") (class "Default")
      (node (ref "Q11") (pin "3") (pinfunction "D_3") (pintype "passive"))
      (node (ref "R29") (pin "2") (pinfunction "2_2") (pintype "passive"))
    )
    (net (code "55") (name "Net-(Q12-D)") (class "Default")
      (node (ref "Q12") (pin "3") (pinfunction "D_3") (pintype "passive"))
      (node (ref "R25") (pin "2") (pinfunction "2_2") (pintype "passive"))
    )
    (net (code "56") (name "Net-(Q12-G)") (class "Default")
      (node (ref "Q12") (pin "1") (pinfunction "G_1") (pintype "passive"))
      (node (ref "Q13") (pin "3") (pinfunction "C_3") (pintype "passive"))
      (node (ref "R38") (pin "2") (pinfunction "2_2") (pintype "passive"))
    )
    (net (code "57") (name "Net-(Q13-B)") (class "Default")
      (node (ref "Q13") (pin "1") (pinfunction "B_1") (pintype "passive"))
      (node (ref "R33") (pin "1") (pinfunction "1_1") (pintype "passive"))
    )
    (net (code "58") (name "Net-(U1A-In+)") (class "Default")
      (node (ref "R11") (pin "1") (pinfunction "1_1") (pintype "passive"))
      (node (ref "U1") (pin "1") (pinfunction "In+_1") (pintype "passive"))
    )
    (net (code "59") (name "Net-(U1A-In-)") (class "Default")
      (node (ref "C10") (pin "1") (pinfunction "1_1") (pintype "passive"))
      (node (ref "R14") (pin "1") (pinfunction "1_1") (pintype "passive"))
      (node (ref "R15") (pin "1") (pinfunction "1_1") (pintype "passive"))
      (node (ref "U1") (pin "3") (pinfunction "In-_3") (pintype "passive"))
    )
    (net (code "60") (name "Net-(U2A-A-)") (class "Default")
      (node (ref "C16") (pin "1") (pinfunction "1_1") (pintype "passive"))
      (node (ref "R24") (pin "2") (pinfunction "2_2") (pintype "passive"))
      (node (ref "R25") (pin "1") (pinfunction "1_1") (pintype "passive"))
      (node (ref "R26") (pin "1") (pinfunction "1_1") (pintype "passive"))
      (node (ref "U2") (pin "2") (pinfunction "A-_2") (pintype "passive"))
    )
    (net (code "61") (name "Net-(U3-1Y0)") (class "Default")
      (node (ref "R32") (pin "1") (pinfunction "1_1") (pintype "passive"))
      (node (ref "U3") (pin "12") (pinfunction "1Y0_12") (pintype "passive"))
    )
    (net (code "62") (name "Net-(U3-1Y1)") (class "Default")
      (node (ref "R35") (pin "1") (pinfunction "1_1") (pintype "passive"))
      (node (ref "U3") (pin "14") (pinfunction "1Y1_14") (pintype "passive"))
    )
    (net (code "63") (name "Net-(U3-1Y2)") (class "Default")
      (node (ref "R34") (pin "1") (pinfunction "1_1") (pintype "passive"))
      (node (ref "U3") (pin "15") (pinfunction "1Y2_15") (pintype "passive"))
    )
    (net (code "64") (name "Net-(U3-1Y3)") (class "Default")
      (node (ref "R36") (pin "1") (pinfunction "1_1") (pintype "passive"))
      (node (ref "U3") (pin "11") (pinfunction "1Y3_11") (pintype "passive"))
    )
    (net (code "65") (name "Vnn") (class "Default")
      (node (ref "C9") (pin "2") (pinfunction "2_2") (pintype "passive"))
      (node (ref "R14") (pin "2") (pinfunction "2_2") (pintype "passive"))
      (node (ref "R17") (pin "1") (pinfunction "1_1") (pintype "passive"))
    )
    (net (code "66") (name "VpCh1") (class "Default")
      (node (ref "Q2") (pin "1") (pinfunction "S1_1") (pintype "passive"))
      (node (ref "Q2") (pin "3") (pinfunction "S2_3") (pintype "passive"))
      (node (ref "R3") (pin "2") (pinfunction "2_2") (pintype "passive"))
      (node (ref "R4") (pin "2") (pinfunction "2_2") (pintype "passive"))
      (node (ref "Z3") (pin "K") (pinfunction "K_K") (pintype "passive"))
      (node (ref "Z4") (pin "K") (pinfunction "K_K") (pintype "passive"))
    )
    (net (code "67") (name "VpCh2") (class "Default")
      (node (ref "Q1") (pin "1") (pinfunction "S1_1") (pintype "passive"))
      (node (ref "Q1") (pin "3") (pinfunction "S2_3") (pintype "passive"))
      (node (ref "R1") (pin "2") (pinfunction "2_2") (pintype "passive"))
      (node (ref "R2") (pin "2") (pinfunction "2_2") (pintype "passive"))
      (node (ref "Z1") (pin "K") (pinfunction "K_K") (pintype "passive"))
      (node (ref "Z2") (pin "K") (pinfunction "K_K") (pintype "passive"))
    )
    (net (code "68") (name "unconnected-(U3-2Y0-Pad1)") (class "Default")
      (node (ref "U3") (pin "1") (pinfunction "2Y0_1") (pintype "passive"))
    )
    (net (code "69") (name "unconnected-(U3-2Y1-Pad5)") (class "Default")
      (node (ref "U3") (pin "5") (pinfunction "2Y1_5") (pintype "passive"))
    )
    (net (code "70") (name "unconnected-(U3-2Y2-Pad2)") (class "Default")
      (node (ref "U3") (pin "2") (pinfunction "2Y2_2") (pintype "passive"))
    )
    (net (code "71") (name "unconnected-(U3-2Y3-Pad4)") (class "Default")
      (node (ref "U3") (pin "4") (pinfunction "2Y3_4") (pintype "passive"))
    )
    (net (code "72") (name "unconnected-(U3-2Z-Pad3)") (class "Default")
      (node (ref "U3") (pin "3") (pinfunction "2Z_3") (pintype "passive"))
    )
    (net (code "73") (name "unconnected-(Z5-PadNC)") (class "Default")
      (node (ref "Z5") (pin "NC") (pinfunction "NC_NC") (pintype "passive"))
    )
  )
)
